# BattPro_InLine.net
KiCad netlist of a schematic drawn in Altium Designer
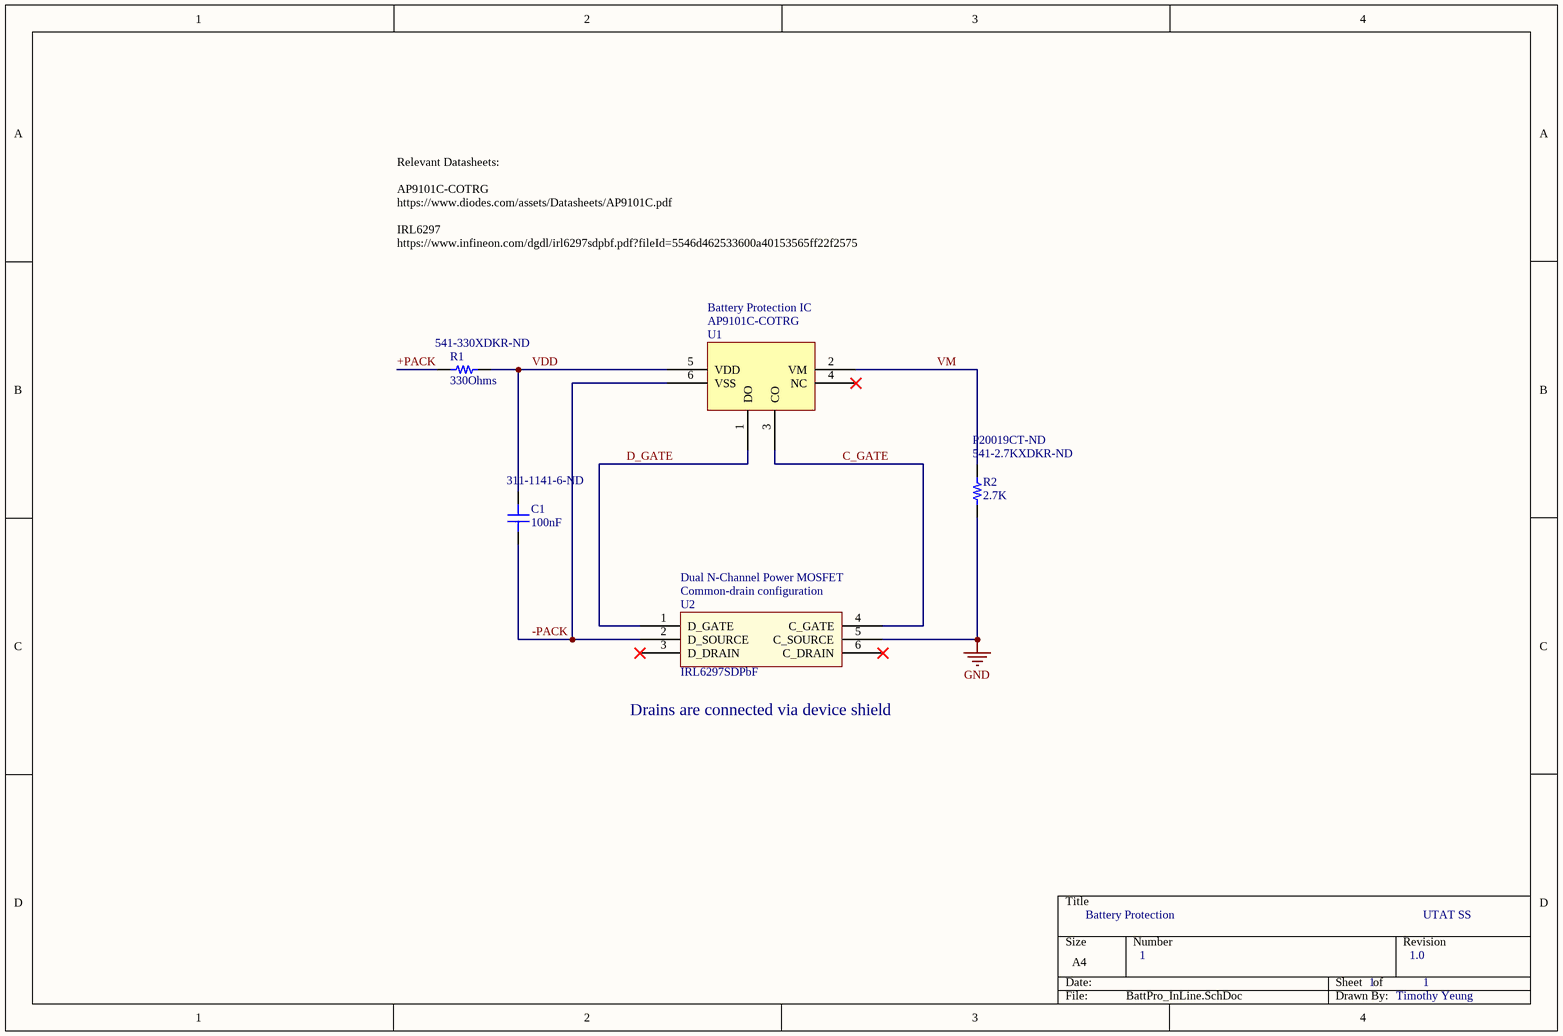
[diagram p0: BattPro_InLine.SchDoc]

(export (version "E")
  (design (tool "Eeschema 10.0.6"))
  (components
    (comp (ref "C1")
      (value "100nF")
      (footprint "CAP0402R")
      (description "SMT Capacitor")
      (fields
        (field (name "SUPPLIER PART NUMBER 1") "311-1141-6-ND")
        (field (name "MANUFACTURER") "Yageo")
        (field (name "MANUFACTURER PART NUMBER") "CC0805KRX7R8BB104")
      )
      (libsource (lib "Passives") (part "Capacitor"))
    )
    (comp (ref "R1")
      (value "330Ohms")
      (footprint "RES0402R")
      (description "SMT Resistor")
      (fields
        (field (name "SUPPLIER PART NUMBER 1") "541-330XDKR-ND")
        (field (name "MANUFACTURER") "Vishay Dale")
        (field (name "MANUFACTURER PART NUMBER") "CRCW2512330RJNEG")
      )
      (libsource (lib "Passives") (part "Resistor"))
    )
    (comp (ref "R2")
      (value "2.7K")
      (footprint "RES0402R")
      (description "SMT Resistor")
      (fields
        (field (name "SUPPLIER PART NUMBER 1") "541-2.7KXDKR-ND")
        (field (name "MANUFACTURER") "Vishay Dale")
        (field (name "MANUFACTURER PART NUMBER") "CRCW25122K70JNEG")
        (field (name "SUPPLIER PART NUMBER 2") "P20019CT-ND")
      )
      (libsource (lib "Passives") (part "Resistor"))
    )
    (comp (ref "U1")
      (value "AP9101C-COTRG")
      (footprint "SOT-26")
      (description "Battery Protection IC")
      (libsource (lib "heron-general") (part "AP9101C-COTRG"))
    )
    (comp (ref "U2")
      (value "IRL6297SDPbF")
      (footprint "IRL6297SDPbF")
      (libsource (lib "heron-general") (part "IRL6297SDPbF"))
    )
  )
  (nets
    (net (code "1") (name "/+PACK") (class "Default")
      (node (ref "R1") (pin "1") (pinfunction "1_1") (pintype "passive"))
    )
    (net (code "2") (name "/-PACK") (class "Default")
      (node (ref "C1") (pin "1") (pinfunction "1_1") (pintype "passive"))
      (node (ref "U1") (pin "6") (pinfunction "VSS_6") (pintype "passive"))
      (node (ref "U2") (pin "2") (pinfunction "D_SOURCE_2") (pintype "passive"))
    )
    (net (code "3") (name "/C_GATE") (class "Default")
      (node (ref "U1") (pin "3") (pinfunction "CO_3") (pintype "passive"))
      (node (ref "U2") (pin "4") (pinfunction "C_GATE_4") (pintype "passive"))
    )
    (net (code "4") (name "/D_GATE") (class "Default")
      (node (ref "U1") (pin "1") (pinfunction "DO_1") (pintype "passive"))
      (node (ref "U2") (pin "1") (pinfunction "D_GATE_1") (pintype "passive"))
    )
    (net (code "5") (name "/VDD") (class "Default")
      (node (ref "C1") (pin "2") (pinfunction "2_2") (pintype "passive"))
      (node (ref "R1") (pin "2") (pinfunction "2_2") (pintype "passive"))
      (node (ref "U1") (pin "5") (pinfunction "VDD_5") (pintype "passive"))
    )
    (net (code "6") (name "/VM") (class "Default")
      (node (ref "R2") (pin "2") (pinfunction "2_2") (pintype "passive"))
      (node (ref "U1") (pin "2") (pinfunction "VM_2") (pintype "passive"))
    )
    (net (code "7") (name "GND") (class "Default")
      (node (ref "R2") (pin "1") (pinfunction "1_1") (pintype "passive"))
      (node (ref "U2") (pin "5") (pinfunction "C_SOURCE_5") (pintype "passive"))
    )
    (net (code "8") (name "unconnected-(U1-NC-Pad4)") (class "Default")
      (node (ref "U1") (pin "4") (pinfunction "NC_4") (pintype "passive+no_connect"))
    )
    (net (code "9") (name "unconnected-(U2-C_DRAIN-Pad6)") (class "Default")
      (node (ref "U2") (pin "6") (pinfunction "C_DRAIN_6") (pintype "passive+no_connect"))
    )
    (net (code "10") (name "unconnected-(U2-D_DRAIN-Pad3)") (class "Default")
      (node (ref "U2") (pin "3") (pinfunction "D_DRAIN_3") (pintype "passive+no_connect"))
    )
  )
)
